# lcd.net
KiCad netlist of a schematic drawn in EAGLE
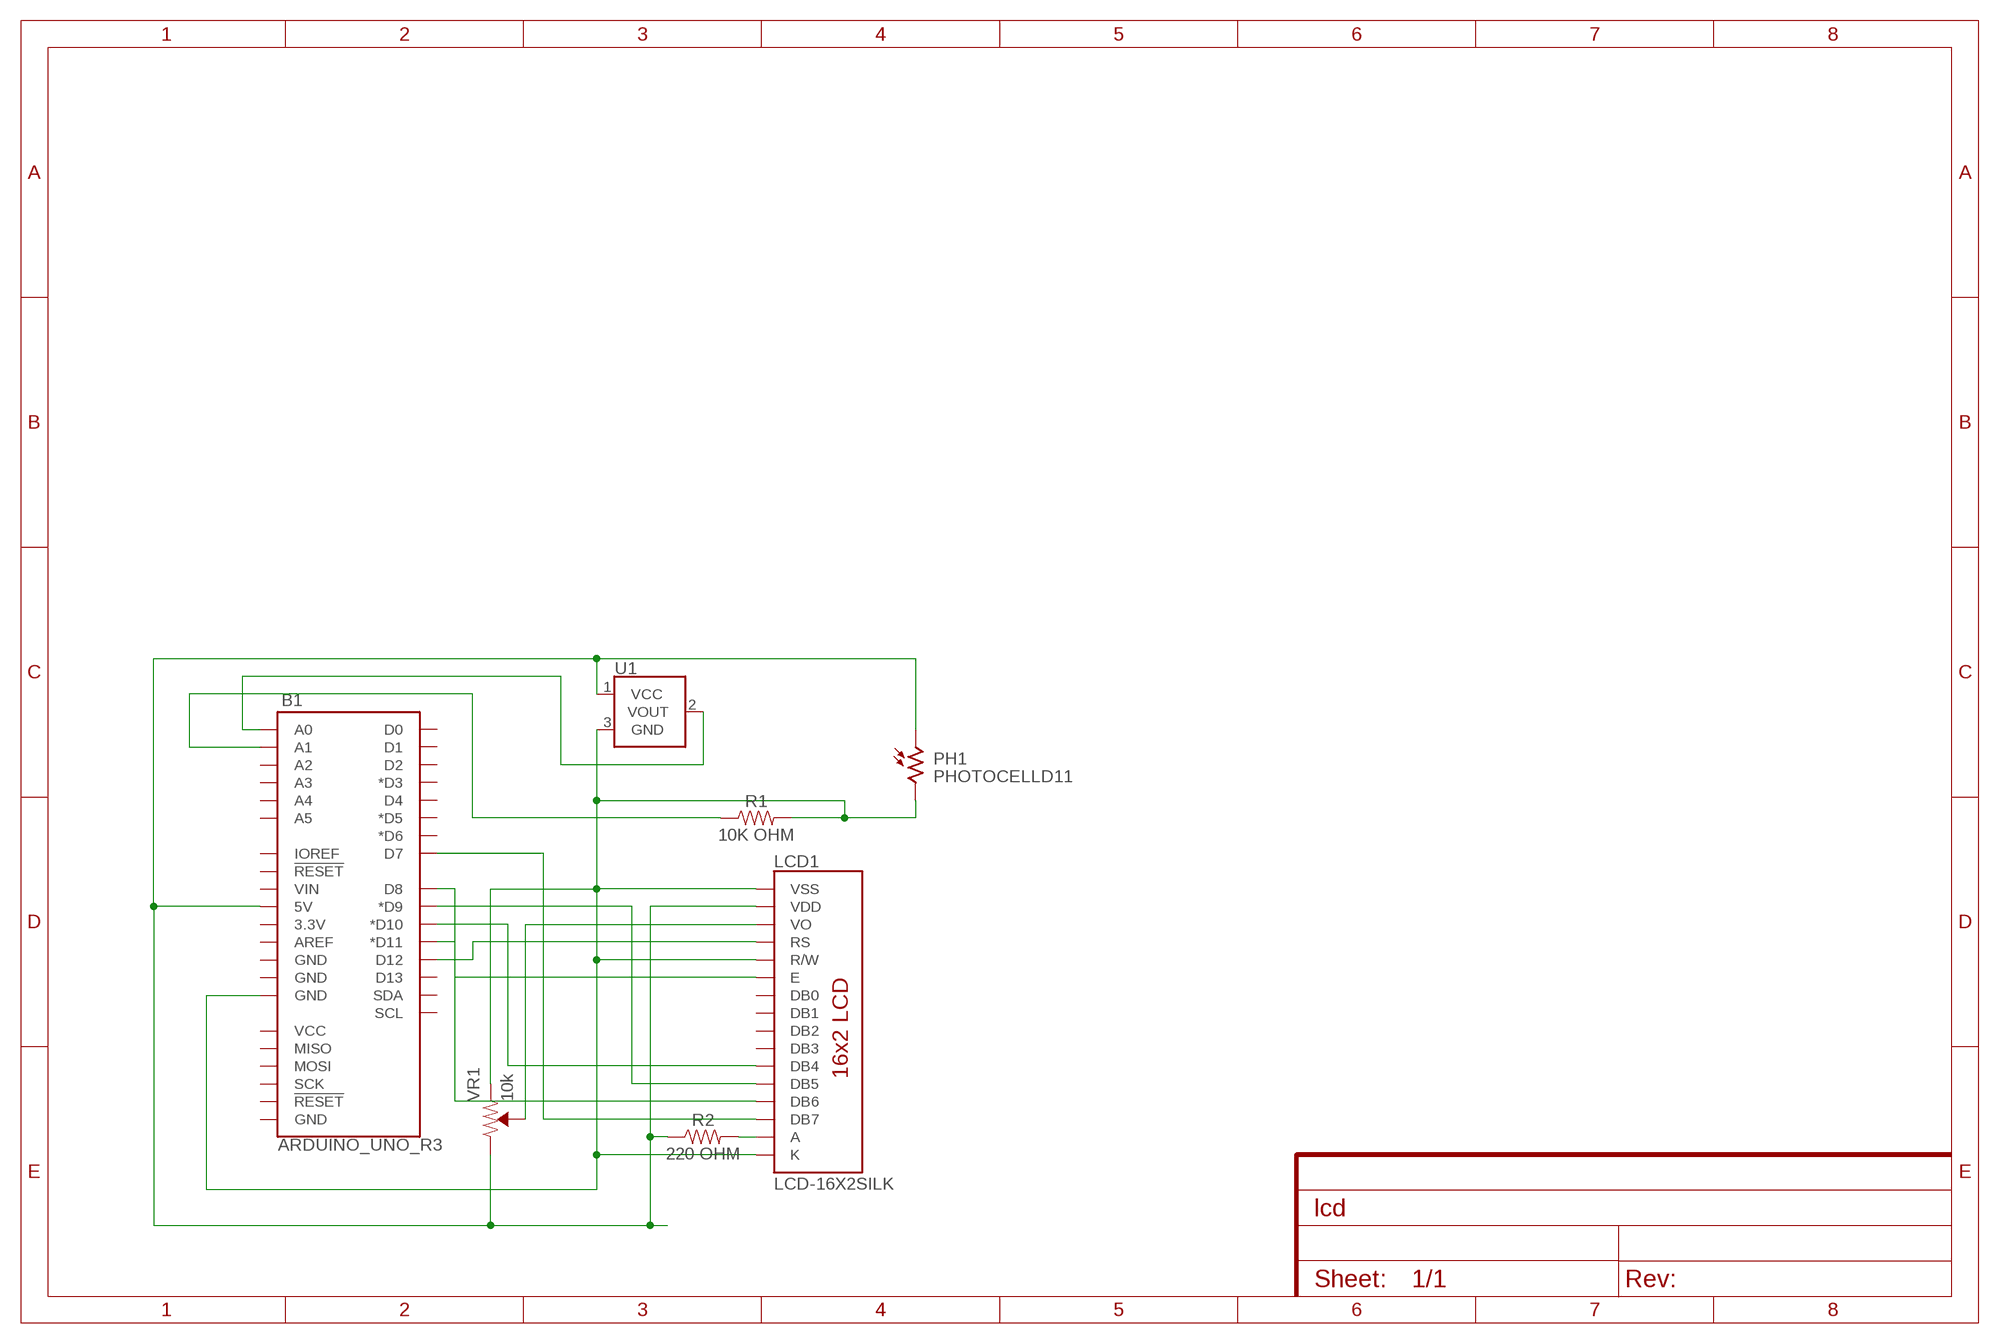
[diagram p0: schematic, sheet 1]

(export (version "E")
  (design (tool "Eeschema 10.0.6"))
  (components
    (comp (ref "B1")
      (value "ARDUINO_UNO_R3")
      (footprint "eagle-import:ARDUINO_R3")
      (libsource (lib "eagle-import") (part "ARDUINO_UNO_R3"))
    )
    (comp (ref "LCD1")
      (value "LCD-16X2SILK")
      (footprint "eagle-import:LCD-16X2")
      (libsource (lib "eagle-import") (part "LCD-16X2SILK"))
    )
    (comp (ref "PH1")
      (value "PHOTOCELLD11")
      (footprint "eagle-import:D11XX_H")
      (libsource (lib "eagle-import") (part "PHOTOCELLD11"))
    )
    (comp (ref "R1")
      (value "10K OHM")
      (footprint "eagle-import:AXIAL-0.3")
      (libsource (lib "eagle-import") (part "RESISTORAXIAL-0.3"))
    )
    (comp (ref "R2")
      (value "220 OHM")
      (footprint "eagle-import:AXIAL-0.3")
      (libsource (lib "eagle-import") (part "RESISTORAXIAL-0.3"))
    )
    (comp (ref "U1")
      (value "TMP36GT9")
      (footprint "eagle-import:TO-92")
      (libsource (lib "eagle-import") (part "TMP36GT9"))
    )
    (comp (ref "VR1")
      (value "10k")
      (footprint "eagle-import:TRIMPOT-PTH-3386U")
      (libsource (lib "eagle-import") (part "TRIMPOT-PTH-10MM-KNOB-1/2W-10%"))
    )
  )
  (nets
    (net (code "1") (name "Net-(B1-*D9)") (class "Default")
      (node (ref "B1") (pin "D9") (pinfunction "*D9_D9") (pintype "bidirectional"))
      (node (ref "LCD1") (pin "12") (pinfunction "DB5_12") (pintype "bidirectional"))
    )
    (net (code "2") (name "Net-(B1-*D10)") (class "Default")
      (node (ref "B1") (pin "D10") (pinfunction "*D10_D10") (pintype "bidirectional"))
      (node (ref "LCD1") (pin "11") (pinfunction "DB4_11") (pintype "bidirectional"))
    )
    (net (code "3") (name "Net-(B1-*D11)") (class "Default")
      (node (ref "B1") (pin "D11") (pinfunction "*D11_D11") (pintype "bidirectional"))
      (node (ref "LCD1") (pin "6") (pinfunction "E_6") (pintype "input"))
    )
    (net (code "4") (name "Net-(LCD1-A)") (class "Default")
      (node (ref "LCD1") (pin "15") (pinfunction "A_15") (pintype "power_in"))
      (node (ref "R2") (pin "P$2") (pinfunction "2_P$2") (pintype "passive"))
    )
    (net (code "5") (name "Net-(LCD1-DB6)") (class "Default")
      (node (ref "B1") (pin "D8") (pinfunction "D8_D8") (pintype "bidirectional"))
      (node (ref "LCD1") (pin "13") (pinfunction "DB6_13") (pintype "bidirectional"))
    )
    (net (code "6") (name "Net-(LCD1-DB7)") (class "Default")
      (node (ref "B1") (pin "D7") (pinfunction "D7_D7") (pintype "bidirectional"))
      (node (ref "LCD1") (pin "14") (pinfunction "DB7_14") (pintype "bidirectional"))
    )
    (net (code "7") (name "Net-(LCD1-K)") (class "Default")
      (node (ref "B1") (pin "GND@2") (pinfunction "GND_GND@2") (pintype "bidirectional"))
      (node (ref "LCD1") (pin "1") (pinfunction "VSS_1") (pintype "power_in"))
      (node (ref "LCD1") (pin "16") (pinfunction "K_16") (pintype "power_in"))
      (node (ref "LCD1") (pin "5") (pinfunction "R/W_5") (pintype "input"))
      (node (ref "PH1") (pin "2") (pinfunction "2_2") (pintype "passive"))
      (node (ref "R1") (pin "P$2") (pinfunction "2_P$2") (pintype "passive"))
      (node (ref "U1") (pin "3") (pinfunction "GND_3") (pintype "bidirectional"))
      (node (ref "VR1") (pin "1") (pinfunction "CCW_1") (pintype "passive"))
    )
    (net (code "8") (name "Net-(LCD1-RS)") (class "Default")
      (node (ref "B1") (pin "D12") (pinfunction "D12_D12") (pintype "bidirectional"))
      (node (ref "LCD1") (pin "4") (pinfunction "RS_4") (pintype "input"))
    )
    (net (code "9") (name "Net-(LCD1-VDD)") (class "Default")
      (node (ref "B1") (pin "5V") (pinfunction "5V_5V") (pintype "bidirectional"))
      (node (ref "LCD1") (pin "2") (pinfunction "VDD_2") (pintype "power_in"))
      (node (ref "PH1") (pin "1") (pinfunction "1_1") (pintype "passive"))
      (node (ref "R2") (pin "P$1") (pinfunction "1_P$1") (pintype "passive"))
      (node (ref "U1") (pin "1") (pinfunction "VCC_1") (pintype "bidirectional"))
      (node (ref "VR1") (pin "3") (pinfunction "CW_3") (pintype "passive"))
    )
    (net (code "10") (name "Net-(LCD1-VO)") (class "Default")
      (node (ref "LCD1") (pin "3") (pinfunction "VO_3") (pintype "bidirectional"))
      (node (ref "VR1") (pin "2") (pinfunction "WIPER_2") (pintype "passive"))
    )
    (net (code "11") (name "Net-(R1-1)") (class "Default")
      (node (ref "B1") (pin "A1") (pinfunction "A1_A1") (pintype "bidirectional"))
      (node (ref "R1") (pin "P$1") (pinfunction "1_P$1") (pintype "passive"))
    )
    (net (code "12") (name "Net-(U1-VOUT)") (class "Default")
      (node (ref "B1") (pin "A0") (pinfunction "A0_A0") (pintype "bidirectional"))
      (node (ref "U1") (pin "2") (pinfunction "VOUT_2") (pintype "bidirectional"))
    )
    (net (code "13") (name "unconnected-(B1-*D3-PadD3)") (class "Default")
      (node (ref "B1") (pin "D3") (pinfunction "*D3_D3") (pintype "bidirectional"))
    )
    (net (code "14") (name "unconnected-(B1-*D5-PadD5)") (class "Default")
      (node (ref "B1") (pin "D5") (pinfunction "*D5_D5") (pintype "bidirectional"))
    )
    (net (code "15") (name "unconnected-(B1-*D6-PadD6)") (class "Default")
      (node (ref "B1") (pin "D6") (pinfunction "*D6_D6") (pintype "bidirectional"))
    )
    (net (code "16") (name "unconnected-(B1-GND-PadGND@1)") (class "Default")
      (node (ref "B1") (pin "GND@1") (pinfunction "GND_GND@1") (pintype "bidirectional"))
    )
    (net (code "17") (name "unconnected-(B1-GND-PadGND@3)") (class "Default")
      (node (ref "B1") (pin "GND@3") (pinfunction "GND_GND@3") (pintype "bidirectional"))
    )
    (net (code "18") (name "unconnected-(B1-GND-PadGND@4)") (class "Default")
      (node (ref "B1") (pin "GND@4") (pinfunction "GND_GND@4") (pintype "bidirectional"))
    )
    (net (code "19") (name "unconnected-(B1-Pad3.3V)") (class "Default")
      (node (ref "B1") (pin "3.3V") (pinfunction "3.3V_3.3V") (pintype "bidirectional"))
    )
    (net (code "20") (name "unconnected-(B1-PadA2)") (class "Default")
      (node (ref "B1") (pin "A2") (pinfunction "A2_A2") (pintype "bidirectional"))
    )
    (net (code "21") (name "unconnected-(B1-PadA3)") (class "Default")
      (node (ref "B1") (pin "A3") (pinfunction "A3_A3") (pintype "bidirectional"))
    )
    (net (code "22") (name "unconnected-(B1-PadA4)") (class "Default")
      (node (ref "B1") (pin "A4") (pinfunction "A4_A4") (pintype "bidirectional"))
    )
    (net (code "23") (name "unconnected-(B1-PadA5)") (class "Default")
      (node (ref "B1") (pin "A5") (pinfunction "A5_A5") (pintype "bidirectional"))
    )
    (net (code "24") (name "unconnected-(B1-PadAREF)") (class "Default")
      (node (ref "B1") (pin "AREF") (pinfunction "AREF_AREF") (pintype "bidirectional"))
    )
    (net (code "25") (name "unconnected-(B1-PadD0)") (class "Default")
      (node (ref "B1") (pin "D0") (pinfunction "D0_D0") (pintype "bidirectional"))
    )
    (net (code "26") (name "unconnected-(B1-PadD1)") (class "Default")
      (node (ref "B1") (pin "D1") (pinfunction "D1_D1") (pintype "bidirectional"))
    )
    (net (code "27") (name "unconnected-(B1-PadD2)") (class "Default")
      (node (ref "B1") (pin "D2") (pinfunction "D2_D2") (pintype "bidirectional"))
    )
    (net (code "28") (name "unconnected-(B1-PadD4)") (class "Default")
      (node (ref "B1") (pin "D4") (pinfunction "D4_D4") (pintype "bidirectional"))
    )
    (net (code "29") (name "unconnected-(B1-PadD13)") (class "Default")
      (node (ref "B1") (pin "D13") (pinfunction "D13_D13") (pintype "bidirectional"))
    )
    (net (code "30") (name "unconnected-(B1-PadIOREF)") (class "Default")
      (node (ref "B1") (pin "IOREF") (pinfunction "IOREF_IOREF") (pintype "bidirectional"))
    )
    (net (code "31") (name "unconnected-(B1-PadMISO)") (class "Default")
      (node (ref "B1") (pin "MISO") (pinfunction "MISO_MISO") (pintype "bidirectional"))
    )
    (net (code "32") (name "unconnected-(B1-PadMOSI)") (class "Default")
      (node (ref "B1") (pin "MOSI") (pinfunction "MOSI_MOSI") (pintype "bidirectional"))
    )
    (net (code "33") (name "unconnected-(B1-PadSCK)") (class "Default")
      (node (ref "B1") (pin "SCK") (pinfunction "SCK_SCK") (pintype "bidirectional"))
    )
    (net (code "34") (name "unconnected-(B1-PadSCL)") (class "Default")
      (node (ref "B1") (pin "SCL") (pinfunction "SCL_SCL") (pintype "bidirectional"))
    )
    (net (code "35") (name "unconnected-(B1-PadSDA)") (class "Default")
      (node (ref "B1") (pin "SDA") (pinfunction "SDA_SDA") (pintype "bidirectional"))
    )
    (net (code "36") (name "unconnected-(B1-PadVCC)") (class "Default")
      (node (ref "B1") (pin "VCC") (pinfunction "VCC_VCC") (pintype "bidirectional"))
    )
    (net (code "37") (name "unconnected-(B1-PadVIN)") (class "Default")
      (node (ref "B1") (pin "VIN") (pinfunction "VIN_VIN") (pintype "bidirectional"))
    )
    (net (code "38") (name "unconnected-(B1-~{RESET}-PadRESET@1)") (class "Default")
      (node (ref "B1") (pin "RESET@1") (pinfunction "~{RESET}_RESET@1") (pintype "bidirectional"))
    )
    (net (code "39") (name "unconnected-(B1-~{RESET}-PadRESET@2)") (class "Default")
      (node (ref "B1") (pin "RESET@2") (pinfunction "~{RESET}_RESET@2") (pintype "bidirectional"))
    )
    (net (code "40") (name "unconnected-(LCD1-DB0-Pad7)") (class "Default")
      (node (ref "LCD1") (pin "7") (pinfunction "DB0_7") (pintype "bidirectional"))
    )
    (net (code "41") (name "unconnected-(LCD1-DB1-Pad8)") (class "Default")
      (node (ref "LCD1") (pin "8") (pinfunction "DB1_8") (pintype "bidirectional"))
    )
    (net (code "42") (name "unconnected-(LCD1-DB2-Pad9)") (class "Default")
      (node (ref "LCD1") (pin "9") (pinfunction "DB2_9") (pintype "bidirectional"))
    )
    (net (code "43") (name "unconnected-(LCD1-DB3-Pad10)") (class "Default")
      (node (ref "LCD1") (pin "10") (pinfunction "DB3_10") (pintype "bidirectional"))
    )
  )
)
